# Flash.net
KiCad netlist of a schematic drawn in Altium Designer
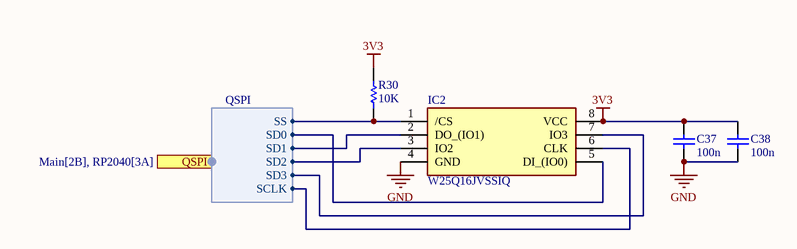
[diagram p0: Flash.SchDoc]

(export (version "E")
  (design (tool "Eeschema 10.0.6"))
  (components
    (comp (ref "C37")
      (value "100n")
      (footprint "CAPC0603(1608)55_N")
      (description "Keramikvielschichtkondensator, SMD, Baureihe MC, ± 20%")
      (fields (field (name "MANUFACTURER") "Multicomp"))
      (libsource (lib "Standardbauteile") (part "Cap 100n"))
    )
    (comp (ref "C38")
      (value "100n")
      (footprint "CAPC0603(1608)55_N")
      (description "Keramikvielschichtkondensator, SMD, Baureihe MC, ± 20%")
      (fields (field (name "MANUFACTURER") "Multicomp"))
      (libsource (lib "Standardbauteile") (part "Cap 100n"))
    )
    (comp (ref "IC2")
      (value "W25Q16JVSSIQ")
      (footprint "Custom Components:SOIC127P790X216-8N")
      (description "Integrated Circuit")
      (fields (field (name "MOUSER PART NUMBER") "454-W25Q16JVSSIQ"))
      (libsource (lib "Custom Components") (part "W25Q16JVSSIQ"))
    )
    (comp (ref "R30")
      (value "10K")
      (footprint "RESC0603(1608)_N")
      (description "Chipwiderstand, SMD, Baureihe MC, 1%")
      (fields (field (name "MANUFACTURER") "Multicomp"))
      (libsource (lib "Standardbauteile") (part "Res 100K"))
    )
  )
  (nets
    (net (code "2") (name "/SCLK") (class "Default")
      (node (ref "IC2") (pin "6") (pinfunction "CLK_6") (pintype "passive"))
    )
    (net (code "3") (name "/SD0") (class "Default")
      (node (ref "IC2") (pin "5") (pinfunction "DI_(IO0)_5") (pintype "passive"))
    )
    (net (code "4") (name "/SD1") (class "Default")
      (node (ref "IC2") (pin "2") (pinfunction "DO_(IO1)_2") (pintype "passive"))
    )
    (net (code "5") (name "/SD2") (class "Default")
      (node (ref "IC2") (pin "3") (pinfunction "IO2_3") (pintype "passive"))
    )
    (net (code "6") (name "/SD3") (class "Default")
      (node (ref "IC2") (pin "7") (pinfunction "IO3_7") (pintype "passive"))
    )
    (net (code "7") (name "/SS") (class "Default")
      (node (ref "IC2") (pin "1") (pinfunction "/CS_1") (pintype "passive"))
      (node (ref "R30") (pin "1") (pinfunction "1_1") (pintype "passive"))
    )
    (net (code "9") (name "3V3") (class "Default")
      (node (ref "C37") (pin "2") (pinfunction "2_2") (pintype "passive"))
      (node (ref "C38") (pin "2") (pinfunction "2_2") (pintype "passive"))
      (node (ref "IC2") (pin "8") (pinfunction "VCC_8") (pintype "passive"))
      (node (ref "R30") (pin "2") (pinfunction "2_2") (pintype "passive"))
    )
    (net (code "10") (name "GND") (class "Default")
      (node (ref "C37") (pin "1") (pinfunction "1_1") (pintype "passive"))
      (node (ref "C38") (pin "1") (pinfunction "1_1") (pintype "passive"))
      (node (ref "IC2") (pin "4") (pinfunction "GND_4") (pintype "passive"))
    )
  )
)
